# MCU.net
KiCad netlist of a schematic drawn in Altium Designer
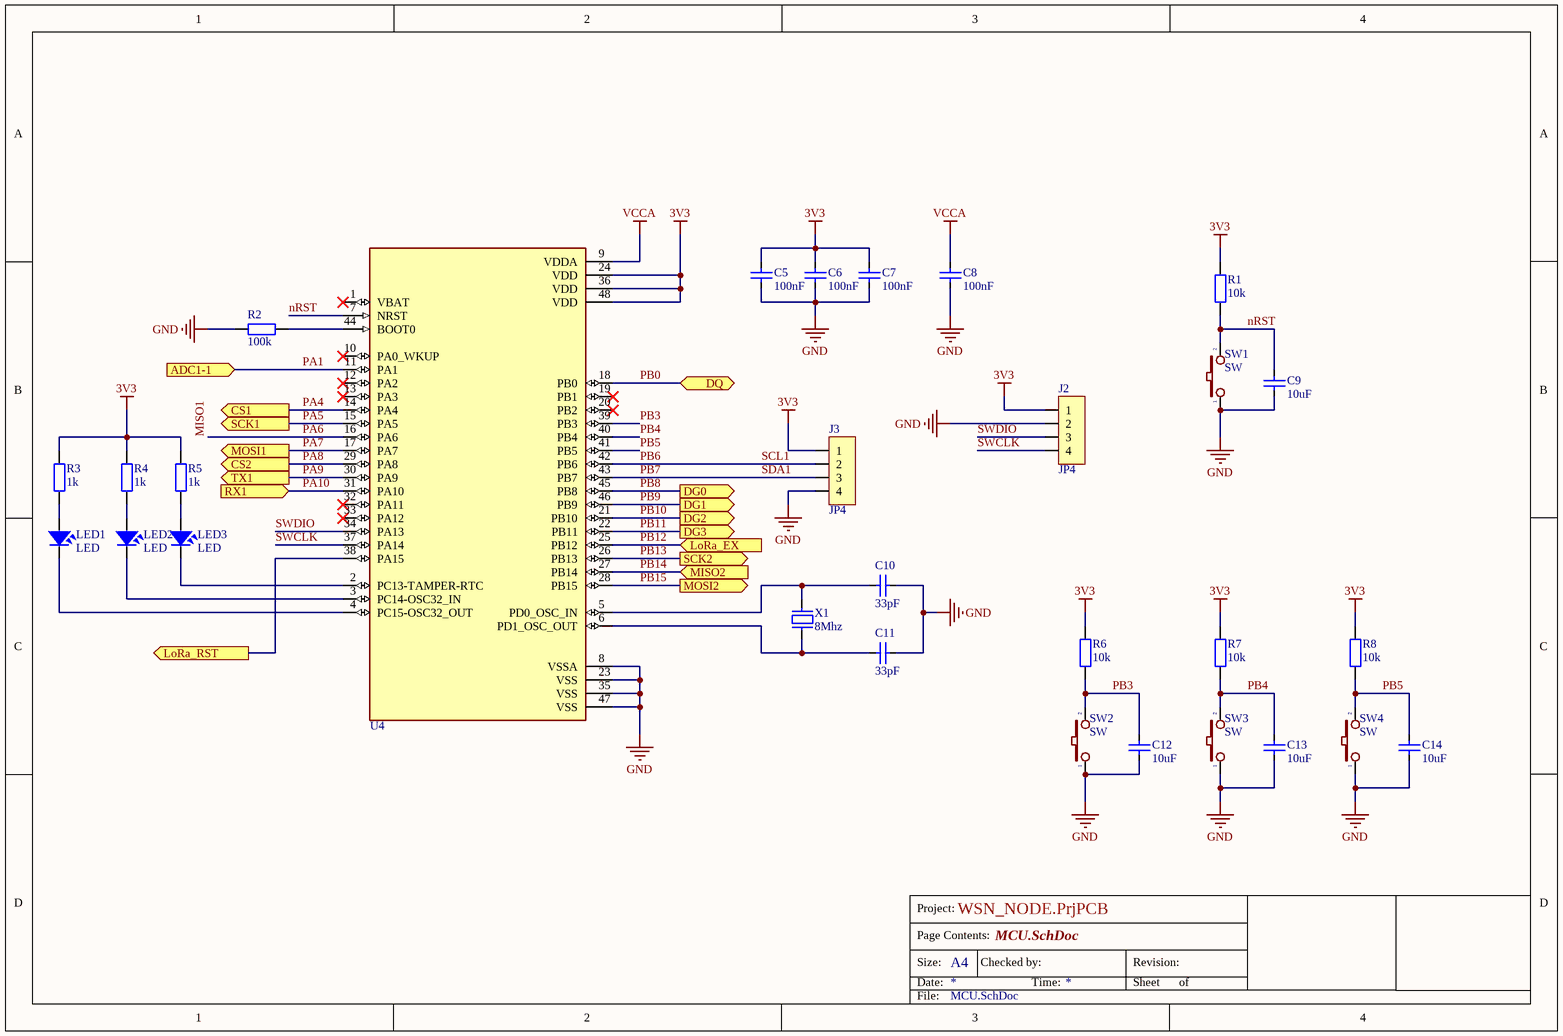
[diagram p0: MCU.SchDoc]

(export (version "E")
  (design (tool "Eeschema 10.0.6"))
  (components
    (comp (ref "C5")
      (value "100nF")
      (footprint "CAP_0805")
      (description "Capacitor")
      (fields (field (name "PUBLISHER") "Altium Limited"))
      (libsource (lib "My Library") (part "CapSMD"))
    )
    (comp (ref "C6")
      (value "100nF")
      (footprint "CAP_0805")
      (description "Capacitor")
      (fields (field (name "PUBLISHER") "Altium Limited"))
      (libsource (lib "My Library") (part "CapSMD"))
    )
    (comp (ref "C7")
      (value "100nF")
      (footprint "CAP_0805")
      (description "Capacitor")
      (fields (field (name "PUBLISHER") "Altium Limited"))
      (libsource (lib "My Library") (part "CapSMD"))
    )
    (comp (ref "C8")
      (value "100nF")
      (footprint "CAP_0805")
      (description "Capacitor")
      (fields (field (name "PUBLISHER") "Altium Limited"))
      (libsource (lib "My Library") (part "CapSMD"))
    )
    (comp (ref "C9")
      (value "10uF")
      (footprint "CAP_0805")
      (description "Capacitor")
      (fields (field (name "PUBLISHER") "Altium Limited"))
      (libsource (lib "My Library") (part "CapSMD"))
    )
    (comp (ref "C10")
      (value "33pF")
      (footprint "CAP_0805")
      (description "Capacitor")
      (fields (field (name "PUBLISHER") "Altium Limited"))
      (libsource (lib "My Library") (part "CapSMD"))
    )
    (comp (ref "C11")
      (value "33pF")
      (footprint "CAP_0805")
      (description "Capacitor")
      (fields (field (name "PUBLISHER") "Altium Limited"))
      (libsource (lib "My Library") (part "CapSMD"))
    )
    (comp (ref "C12")
      (value "10uF")
      (footprint "CAP_0805")
      (description "Capacitor")
      (fields (field (name "PUBLISHER") "Altium Limited"))
      (libsource (lib "My Library") (part "CapSMD"))
    )
    (comp (ref "C13")
      (value "10uF")
      (footprint "CAP_0805")
      (description "Capacitor")
      (fields (field (name "PUBLISHER") "Altium Limited"))
      (libsource (lib "My Library") (part "CapSMD"))
    )
    (comp (ref "C14")
      (value "10uF")
      (footprint "CAP_0805")
      (description "Capacitor")
      (fields (field (name "PUBLISHER") "Altium Limited"))
      (libsource (lib "My Library") (part "CapSMD"))
    )
    (comp (ref "J2")
      (value "JP4")
      (footprint "JP4-C1T")
      (description "WR-PHD 2.54 mm Angled Socket Header")
      (fields
        (field (name "MANUFACTURER") "Würth Elektronik eiSos GmbH")
        (field (name "PARTNO") "613004143121")
        (field (name "CREATED BY") "Karrer Zheng")
      )
      (libsource (lib "My Library") (part "JP4"))
    )
    (comp (ref "J3")
      (value "JP4")
      (footprint "JP4-C1T")
      (description "WR-PHD 2.54 mm Angled Socket Header")
      (fields
        (field (name "MANUFACTURER") "Würth Elektronik eiSos GmbH")
        (field (name "PARTNO") "613004143121")
        (field (name "CREATED BY") "Karrer Zheng")
      )
      (libsource (lib "My Library") (part "JP4"))
    )
    (comp (ref "LED1")
      (value "LED")
      (footprint "LED-0805-Red")
      (description "LED Single colour Green and Red")
      (libsource (lib "My Library") (part "LED"))
    )
    (comp (ref "LED2")
      (value "LED")
      (footprint "LED-0805-Yellow")
      (description "LED Single colour Green and Red")
      (libsource (lib "My Library") (part "LED"))
    )
    (comp (ref "LED3")
      (value "LED")
      (footprint "LED-0805-Green")
      (description "LED Single colour Green and Red")
      (libsource (lib "My Library") (part "LED"))
    )
    (comp (ref "R1")
      (value "10k")
      (footprint "RES-SMD-0805")
      (description "Resistor SMD")
      (fields
        (field (name "MANUFACTURER") "Generic Components")
        (field (name "PUBLISHER") "Altium Hobart Technology Centre")
      )
      (libsource (lib "My Library") (part "Resistor - SMD"))
    )
    (comp (ref "R2")
      (value "100k")
      (footprint "RES-SMD-0805")
      (description "Resistor SMD")
      (fields
        (field (name "MANUFACTURER") "Generic Components")
        (field (name "PUBLISHER") "Altium Hobart Technology Centre")
      )
      (libsource (lib "My Library") (part "Resistor - SMD"))
    )
    (comp (ref "R3")
      (value "1k")
      (footprint "RES-SMD-0805")
      (description "Resistor SMD")
      (fields
        (field (name "MANUFACTURER") "Generic Components")
        (field (name "PUBLISHER") "Altium Hobart Technology Centre")
      )
      (libsource (lib "My Library") (part "Resistor - SMD"))
    )
    (comp (ref "R4")
      (value "1k")
      (footprint "RES-SMD-0805")
      (description "Resistor SMD")
      (fields
        (field (name "MANUFACTURER") "Generic Components")
        (field (name "PUBLISHER") "Altium Hobart Technology Centre")
      )
      (libsource (lib "My Library") (part "Resistor - SMD"))
    )
    (comp (ref "R5")
      (value "1k")
      (footprint "RES-SMD-0805")
      (description "Resistor SMD")
      (fields
        (field (name "MANUFACTURER") "Generic Components")
        (field (name "PUBLISHER") "Altium Hobart Technology Centre")
      )
      (libsource (lib "My Library") (part "Resistor - SMD"))
    )
    (comp (ref "R6")
      (value "10k")
      (footprint "RES-SMD-0805")
      (description "Resistor SMD")
      (fields
        (field (name "MANUFACTURER") "Generic Components")
        (field (name "PUBLISHER") "Altium Hobart Technology Centre")
      )
      (libsource (lib "My Library") (part "Resistor - SMD"))
    )
    (comp (ref "R7")
      (value "10k")
      (footprint "RES-SMD-0805")
      (description "Resistor SMD")
      (fields
        (field (name "MANUFACTURER") "Generic Components")
        (field (name "PUBLISHER") "Altium Hobart Technology Centre")
      )
      (libsource (lib "My Library") (part "Resistor - SMD"))
    )
    (comp (ref "R8")
      (value "10k")
      (footprint "RES-SMD-0805")
      (description "Resistor SMD")
      (fields
        (field (name "MANUFACTURER") "Generic Components")
        (field (name "PUBLISHER") "Altium Hobart Technology Centre")
      )
      (libsource (lib "My Library") (part "Resistor - SMD"))
    )
    (comp (ref "SW1")
      (value "SW")
      (footprint "SW 3x2x4")
      (description "Switch button 2 pin")
      (libsource (lib "My Library") (part "SW2"))
    )
    (comp (ref "SW2")
      (value "SW")
      (footprint "SW2")
      (description "Switch button 2 pin")
      (libsource (lib "My Library") (part "SW2"))
    )
    (comp (ref "SW3")
      (value "SW")
      (footprint "SW2")
      (description "Switch button 2 pin")
      (libsource (lib "My Library") (part "SW2"))
    )
    (comp (ref "SW4")
      (value "SW")
      (footprint "SW2")
      (description "Switch button 2 pin")
      (libsource (lib "My Library") (part "SW2"))
    )
    (comp (ref "U4")
      (value "STM32")
      (footprint "LQFP 48")
      (description "STM32 ARM-based 32-bit MCU with 64 Kbytes Flash, 64-pin LQFP, Industrial Temperature")
      (libsource (lib "My Library") (part "STM32F103C8T6"))
    )
    (comp (ref "X1")
      (value "8Mhz")
      (footprint "XTAL 5032 SMD")
      (description "Crystal For all Crystal 2pin.")
      (libsource (lib "My Library") (part "XT2"))
    )
  )
  (nets
    (net (code "1") (name "/LoRa_RST") (class "Default")
      (node (ref "U4") (pin "38") (pinfunction "PA15_38") (pintype "bidirectional"))
    )
    (net (code "2") (name "/MISO1") (class "Default")
      (node (ref "U4") (pin "16") (pinfunction "PA6_16") (pintype "bidirectional"))
    )
    (net (code "3") (name "/PA1") (class "Default")
      (node (ref "U4") (pin "11") (pinfunction "PA1_11") (pintype "bidirectional"))
    )
    (net (code "4") (name "/PA4") (class "Default")
      (node (ref "U4") (pin "14") (pinfunction "PA4_14") (pintype "bidirectional"))
    )
    (net (code "5") (name "/PA5") (class "Default")
      (node (ref "U4") (pin "15") (pinfunction "PA5_15") (pintype "bidirectional"))
    )
    (net (code "6") (name "/PA7") (class "Default")
      (node (ref "U4") (pin "17") (pinfunction "PA7_17") (pintype "bidirectional"))
    )
    (net (code "7") (name "/PA8") (class "Default")
      (node (ref "U4") (pin "29") (pinfunction "PA8_29") (pintype "bidirectional"))
    )
    (net (code "8") (name "/PA9") (class "Default")
      (node (ref "U4") (pin "30") (pinfunction "PA9_30") (pintype "bidirectional"))
    )
    (net (code "9") (name "/PA10") (class "Default")
      (node (ref "U4") (pin "31") (pinfunction "PA10_31") (pintype "bidirectional"))
    )
    (net (code "10") (name "/PB0") (class "Default")
      (node (ref "U4") (pin "18") (pinfunction "PB0_18") (pintype "bidirectional"))
    )
    (net (code "11") (name "/PB3") (class "Default")
      (node (ref "C12") (pin "2") (pinfunction "2_2") (pintype "passive"))
      (node (ref "R6") (pin "2") (pinfunction "2_2") (pintype "passive"))
      (node (ref "SW2") (pin "2") (pinfunction "2_2") (pintype "passive"))
      (node (ref "U4") (pin "39") (pinfunction "PB3_39") (pintype "bidirectional"))
    )
    (net (code "12") (name "/PB4") (class "Default")
      (node (ref "C13") (pin "2") (pinfunction "2_2") (pintype "passive"))
      (node (ref "R7") (pin "2") (pinfunction "2_2") (pintype "passive"))
      (node (ref "SW3") (pin "2") (pinfunction "2_2") (pintype "passive"))
      (node (ref "U4") (pin "40") (pinfunction "PB4_40") (pintype "bidirectional"))
    )
    (net (code "13") (name "/PB5") (class "Default")
      (node (ref "C14") (pin "2") (pinfunction "2_2") (pintype "passive"))
      (node (ref "R8") (pin "2") (pinfunction "2_2") (pintype "passive"))
      (node (ref "SW4") (pin "2") (pinfunction "2_2") (pintype "passive"))
      (node (ref "U4") (pin "41") (pinfunction "PB5_41") (pintype "bidirectional"))
    )
    (net (code "14") (name "/PB6") (class "Default")
      (node (ref "J3") (pin "2") (pinfunction "2_2") (pintype "passive"))
      (node (ref "U4") (pin "42") (pinfunction "PB6_42") (pintype "bidirectional"))
    )
    (net (code "15") (name "/PB7") (class "Default")
      (node (ref "J3") (pin "3") (pinfunction "3_3") (pintype "passive"))
      (node (ref "U4") (pin "43") (pinfunction "PB7_43") (pintype "bidirectional"))
    )
    (net (code "16") (name "/PB8") (class "Default")
      (node (ref "U4") (pin "45") (pinfunction "PB8_45") (pintype "bidirectional"))
    )
    (net (code "17") (name "/PB9") (class "Default")
      (node (ref "U4") (pin "46") (pinfunction "PB9_46") (pintype "bidirectional"))
    )
    (net (code "18") (name "/PB10") (class "Default")
      (node (ref "U4") (pin "21") (pinfunction "PB10_21") (pintype "bidirectional"))
    )
    (net (code "19") (name "/PB11") (class "Default")
      (node (ref "U4") (pin "22") (pinfunction "PB11_22") (pintype "bidirectional"))
    )
    (net (code "20") (name "/PB12") (class "Default")
      (node (ref "U4") (pin "25") (pinfunction "PB12_25") (pintype "bidirectional"))
    )
    (net (code "21") (name "/PB13") (class "Default")
      (node (ref "U4") (pin "26") (pinfunction "PB13_26") (pintype "bidirectional"))
    )
    (net (code "22") (name "/PB14") (class "Default")
      (node (ref "U4") (pin "27") (pinfunction "PB14_27") (pintype "bidirectional"))
    )
    (net (code "23") (name "/PB15") (class "Default")
      (node (ref "U4") (pin "28") (pinfunction "PB15_28") (pintype "bidirectional"))
    )
    (net (code "24") (name "/SWCLK") (class "Default")
      (node (ref "J2") (pin "4") (pinfunction "4_4") (pintype "passive"))
      (node (ref "U4") (pin "37") (pinfunction "PA14_37") (pintype "bidirectional"))
    )
    (net (code "25") (name "/SWDIO") (class "Default")
      (node (ref "J2") (pin "3") (pinfunction "3_3") (pintype "passive"))
      (node (ref "U4") (pin "34") (pinfunction "PA13_34") (pintype "bidirectional"))
    )
    (net (code "26") (name "/nRST") (class "Default")
      (node (ref "C9") (pin "2") (pinfunction "2_2") (pintype "passive"))
      (node (ref "R1") (pin "2") (pinfunction "2_2") (pintype "passive"))
      (node (ref "SW1") (pin "2") (pinfunction "2_2") (pintype "passive"))
      (node (ref "U4") (pin "7") (pinfunction "NRST_7") (pintype "input"))
    )
    (net (code "27") (name "3V3") (class "Default")
      (node (ref "C5") (pin "2") (pinfunction "2_2") (pintype "passive"))
      (node (ref "C6") (pin "2") (pinfunction "2_2") (pintype "passive"))
      (node (ref "C7") (pin "2") (pinfunction "2_2") (pintype "passive"))
      (node (ref "J2") (pin "1") (pinfunction "1_1") (pintype "passive"))
      (node (ref "J3") (pin "1") (pinfunction "1_1") (pintype "passive"))
      (node (ref "R1") (pin "1") (pinfunction "1_1") (pintype "passive"))
      (node (ref "R3") (pin "1") (pinfunction "1_1") (pintype "passive"))
      (node (ref "R4") (pin "1") (pinfunction "1_1") (pintype "passive"))
      (node (ref "R5") (pin "1") (pinfunction "1_1") (pintype "passive"))
      (node (ref "R6") (pin "1") (pinfunction "1_1") (pintype "passive"))
      (node (ref "R7") (pin "1") (pinfunction "1_1") (pintype "passive"))
      (node (ref "R8") (pin "1") (pinfunction "1_1") (pintype "passive"))
      (node (ref "U4") (pin "24") (pinfunction "VDD_24") (pintype "power_in"))
      (node (ref "U4") (pin "36") (pinfunction "VDD_36") (pintype "power_in"))
      (node (ref "U4") (pin "48") (pinfunction "VDD_48") (pintype "power_in"))
    )
    (net (code "28") (name "GND") (class "Default")
      (node (ref "C10") (pin "2") (pinfunction "2_2") (pintype "passive"))
      (node (ref "C11") (pin "2") (pinfunction "2_2") (pintype "passive"))
      (node (ref "C12") (pin "1") (pinfunction "1_1") (pintype "passive"))
      (node (ref "C13") (pin "1") (pinfunction "1_1") (pintype "passive"))
      (node (ref "C14") (pin "1") (pinfunction "1_1") (pintype "passive"))
      (node (ref "C5") (pin "1") (pinfunction "1_1") (pintype "passive"))
      (node (ref "C6") (pin "1") (pinfunction "1_1") (pintype "passive"))
      (node (ref "C7") (pin "1") (pinfunction "1_1") (pintype "passive"))
      (node (ref "C8") (pin "1") (pinfunction "1_1") (pintype "passive"))
      (node (ref "C9") (pin "1") (pinfunction "1_1") (pintype "passive"))
      (node (ref "J2") (pin "2") (pinfunction "2_2") (pintype "passive"))
      (node (ref "J3") (pin "4") (pinfunction "4_4") (pintype "passive"))
      (node (ref "R2") (pin "1") (pinfunction "1_1") (pintype "passive"))
      (node (ref "SW1") (pin "1") (pinfunction "1_1") (pintype "passive"))
      (node (ref "SW2") (pin "1") (pinfunction "1_1") (pintype "passive"))
      (node (ref "SW3") (pin "1") (pinfunction "1_1") (pintype "passive"))
      (node (ref "SW4") (pin "1") (pinfunction "1_1") (pintype "passive"))
      (node (ref "U4") (pin "23") (pinfunction "VSS_23") (pintype "power_in"))
      (node (ref "U4") (pin "35") (pinfunction "VSS_35") (pintype "power_in"))
      (node (ref "U4") (pin "47") (pinfunction "VSS_47") (pintype "power_in"))
      (node (ref "U4") (pin "8") (pinfunction "VSSA_8") (pintype "power_in"))
    )
    (net (code "29") (name "Net-(LED1-Pad1)") (class "Default")
      (node (ref "LED1") (pin "1") (pinfunction "1_1") (pintype "passive"))
      (node (ref "R3") (pin "2") (pinfunction "2_2") (pintype "passive"))
    )
    (net (code "30") (name "Net-(LED2-Pad1)") (class "Default")
      (node (ref "LED2") (pin "1") (pinfunction "1_1") (pintype "passive"))
      (node (ref "R4") (pin "2") (pinfunction "2_2") (pintype "passive"))
    )
    (net (code "31") (name "Net-(LED3-Pad1)") (class "Default")
      (node (ref "LED3") (pin "1") (pinfunction "1_1") (pintype "passive"))
      (node (ref "R5") (pin "2") (pinfunction "2_2") (pintype "passive"))
    )
    (net (code "32") (name "Net-(U4-BOOT0)") (class "Default")
      (node (ref "R2") (pin "2") (pinfunction "2_2") (pintype "passive"))
      (node (ref "U4") (pin "44") (pinfunction "BOOT0_44") (pintype "input"))
    )
    (net (code "33") (name "Net-(U4-PC13-TAMPER-RTC)") (class "Default")
      (node (ref "LED3") (pin "2") (pinfunction "2_2") (pintype "passive"))
      (node (ref "U4") (pin "2") (pinfunction "PC13-TAMPER-RTC_2") (pintype "bidirectional"))
    )
    (net (code "34") (name "Net-(U4-PC14-OSC32_IN)") (class "Default")
      (node (ref "LED2") (pin "2") (pinfunction "2_2") (pintype "passive"))
      (node (ref "U4") (pin "3") (pinfunction "PC14-OSC32_IN_3") (pintype "bidirectional"))
    )
    (net (code "35") (name "Net-(U4-PC15-OSC32_OUT)") (class "Default")
      (node (ref "LED1") (pin "2") (pinfunction "2_2") (pintype "passive"))
      (node (ref "U4") (pin "4") (pinfunction "PC15-OSC32_OUT_4") (pintype "bidirectional"))
    )
    (net (code "36") (name "Net-(U4-PD0_OSC_IN)") (class "Default")
      (node (ref "C10") (pin "1") (pinfunction "1_1") (pintype "passive"))
      (node (ref "U4") (pin "5") (pinfunction "PD0_OSC_IN_5") (pintype "bidirectional"))
      (node (ref "X1") (pin "2") (pinfunction "2_2") (pintype "passive"))
    )
    (net (code "37") (name "Net-(U4-PD1_OSC_OUT)") (class "Default")
      (node (ref "C11") (pin "1") (pinfunction "1_1") (pintype "passive"))
      (node (ref "U4") (pin "6") (pinfunction "PD1_OSC_OUT_6") (pintype "bidirectional"))
      (node (ref "X1") (pin "1") (pinfunction "1_1") (pintype "passive"))
    )
    (net (code "38") (name "VCCA") (class "Default")
      (node (ref "C8") (pin "2") (pinfunction "2_2") (pintype "passive"))
      (node (ref "U4") (pin "9") (pinfunction "VDDA_9") (pintype "power_in"))
    )
    (net (code "39") (name "unconnected-(U4-PA0_WKUP-Pad10)") (class "Default")
      (node (ref "U4") (pin "10") (pinfunction "PA0_WKUP_10") (pintype "bidirectional+no_connect"))
    )
    (net (code "40") (name "unconnected-(U4-PA2-Pad12)") (class "Default")
      (node (ref "U4") (pin "12") (pinfunction "PA2_12") (pintype "bidirectional+no_connect"))
    )
    (net (code "41") (name "unconnected-(U4-PA3-Pad13)") (class "Default")
      (node (ref "U4") (pin "13") (pinfunction "PA3_13") (pintype "bidirectional+no_connect"))
    )
    (net (code "42") (name "unconnected-(U4-PA11-Pad32)") (class "Default")
      (node (ref "U4") (pin "32") (pinfunction "PA11_32") (pintype "bidirectional+no_connect"))
    )
    (net (code "43") (name "unconnected-(U4-PA12-Pad33)") (class "Default")
      (node (ref "U4") (pin "33") (pinfunction "PA12_33") (pintype "bidirectional+no_connect"))
    )
    (net (code "44") (name "unconnected-(U4-PB1-Pad19)") (class "Default")
      (node (ref "U4") (pin "19") (pinfunction "PB1_19") (pintype "bidirectional+no_connect"))
    )
    (net (code "45") (name "unconnected-(U4-PB2-Pad20)") (class "Default")
      (node (ref "U4") (pin "20") (pinfunction "PB2_20") (pintype "bidirectional+no_connect"))
    )
    (net (code "46") (name "unconnected-(U4-VBAT-Pad1)") (class "Default")
      (node (ref "U4") (pin "1") (pinfunction "VBAT_1") (pintype "bidirectional+no_connect"))
    )
  )
)
